# draft1.net
KiCad netlist of a schematic drawn in EAGLE
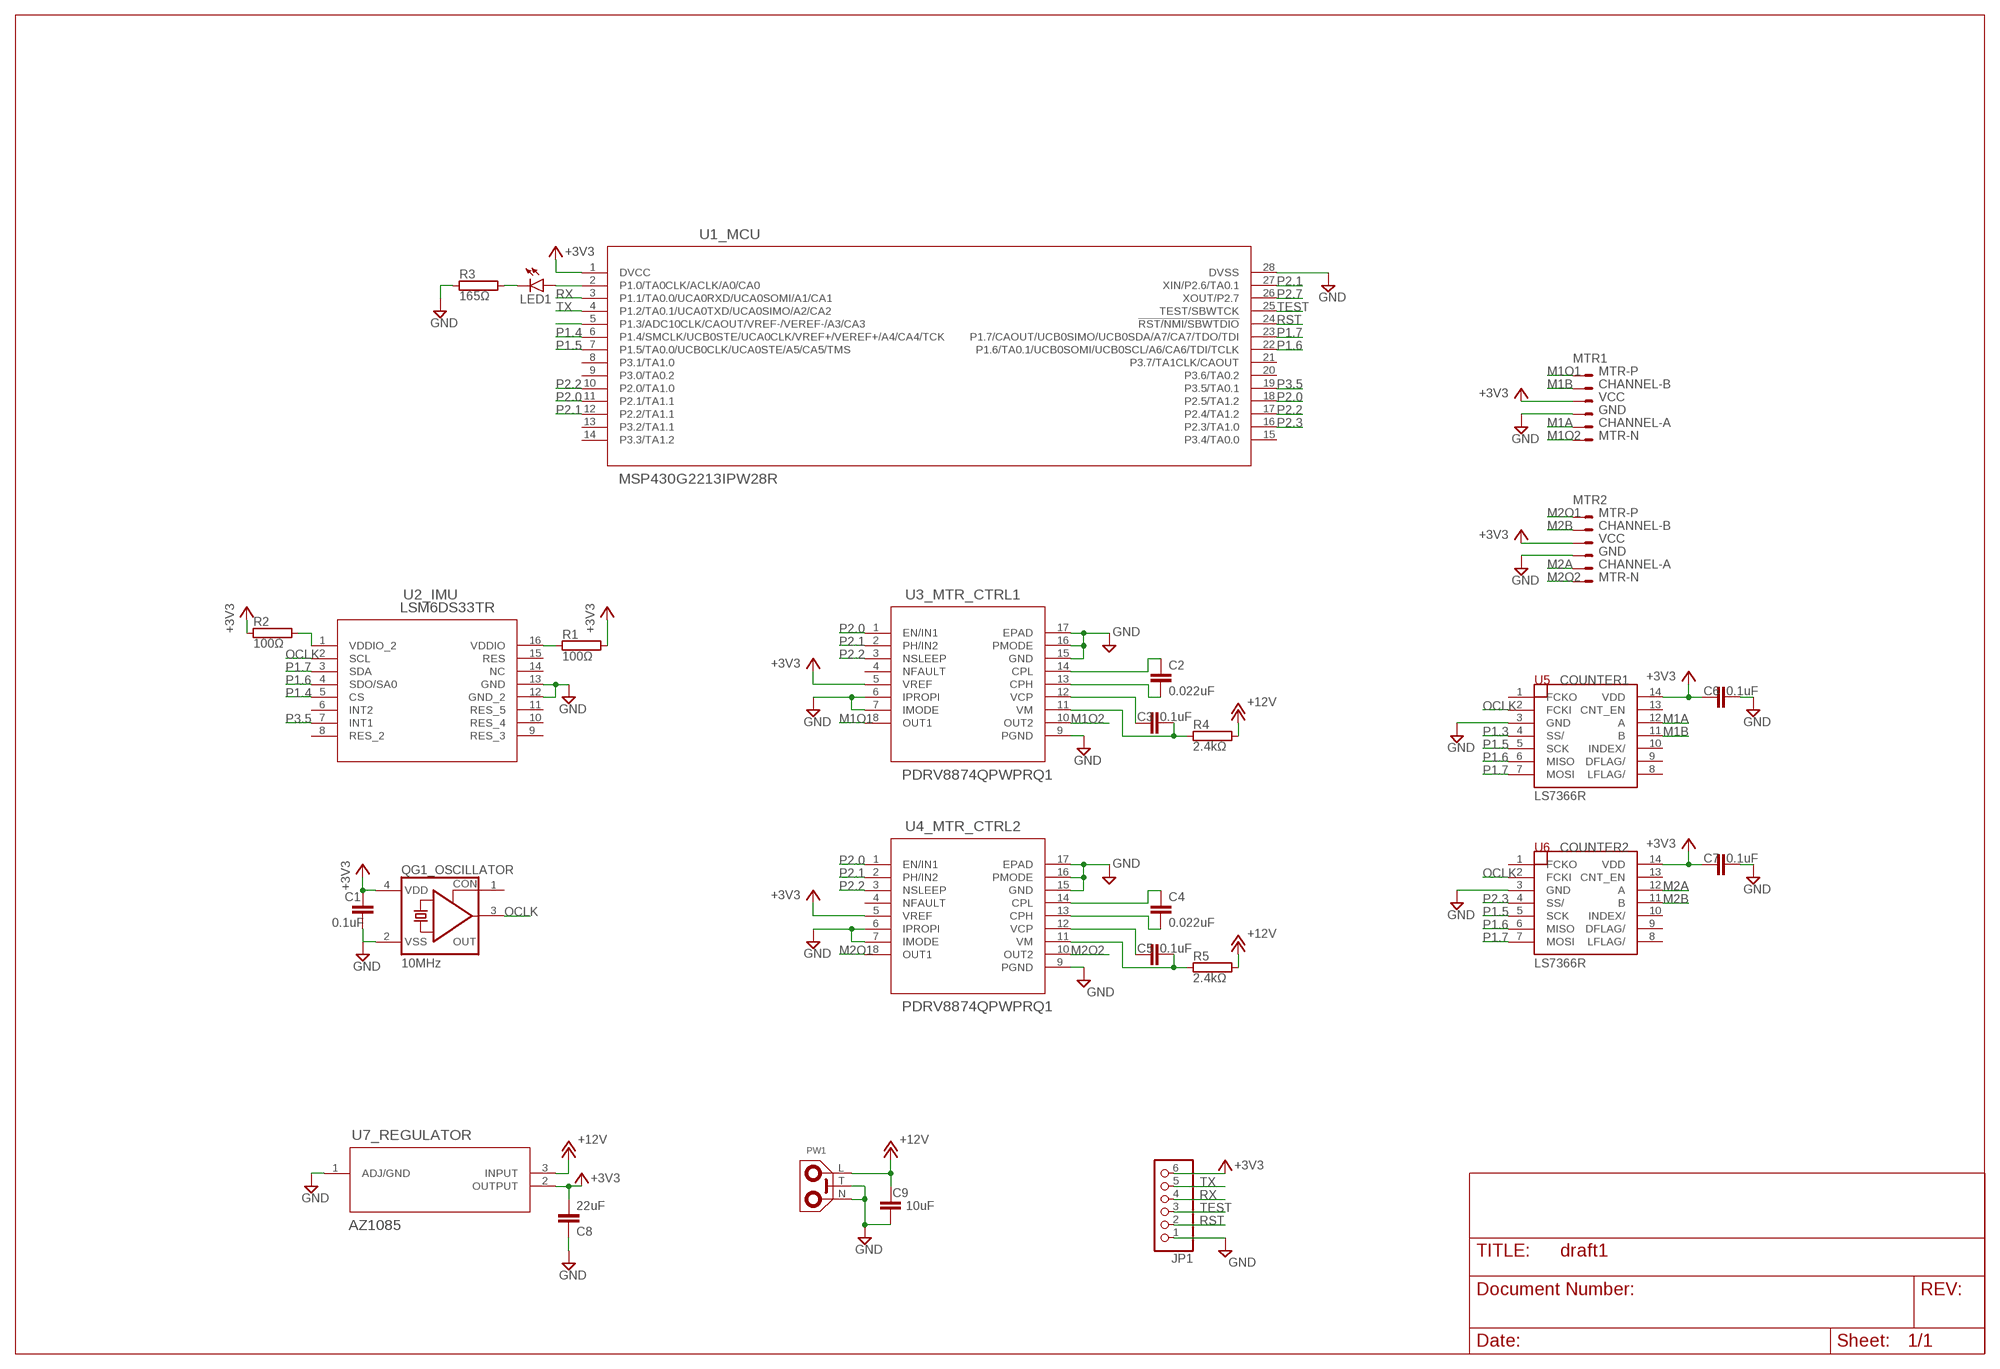
[diagram p0: schematic, sheet 1]

(export (version "E")
  (design (tool "Eeschema 10.0.6"))
  (components
    (comp (ref "C1")
      (value "0.1uF")
      (footprint "eagle-import:C2.5-2")
      (libsource (lib "eagle-import") (part "C2.5/2"))
    )
    (comp (ref "C2")
      (value "0.022uF")
      (footprint "eagle-import:C2.5-2")
      (libsource (lib "eagle-import") (part "C2.5/2"))
    )
    (comp (ref "C3")
      (value "0.1uF")
      (footprint "eagle-import:C2.5-2")
      (libsource (lib "eagle-import") (part "C2.5/2"))
    )
    (comp (ref "C4")
      (value "0.022uF")
      (footprint "eagle-import:C2.5-2")
      (libsource (lib "eagle-import") (part "C2.5/2"))
    )
    (comp (ref "C5")
      (value "0.1uF")
      (footprint "eagle-import:C2.5-2")
      (libsource (lib "eagle-import") (part "C2.5/2"))
    )
    (comp (ref "C6")
      (value "0.1uF")
      (footprint "eagle-import:C2.5-2")
      (libsource (lib "eagle-import") (part "C2.5/2"))
    )
    (comp (ref "C7")
      (value "0.1uF")
      (footprint "eagle-import:C2.5-2")
      (libsource (lib "eagle-import") (part "C2.5/2"))
    )
    (comp (ref "C8")
      (value "22uF")
      (footprint "eagle-import:C2.5-2")
      (libsource (lib "eagle-import") (part "C2.5/2"))
    )
    (comp (ref "C9")
      (value "10uF")
      (footprint "eagle-import:C2.5-2")
      (libsource (lib "eagle-import") (part "C2.5/2"))
    )
    (comp (ref "JP1")
      (value "PINHD-1X6")
      (footprint "eagle-import:1X06")
      (libsource (lib "eagle-import") (part "PINHD-1X6"))
    )
    (comp (ref "LED1")
      (value "LED5MM")
      (footprint "eagle-import:LED5MM")
      (libsource (lib "eagle-import") (part "LED5MM"))
    )
    (comp (ref "MTR1")
      (value "JST-XH-06-PIN-ROUND-PAD")
      (footprint "eagle-import:JST-XH-06-PACKAGE-ROUND-PAD")
      (fields (field (name "MTR1") "1"))
      (libsource (lib "eagle-import") (part "JST-XH-06-PIN-ROUND-PAD"))
    )
    (comp (ref "MTR2")
      (value "JST-XH-06-PIN-ROUND-PAD")
      (footprint "eagle-import:JST-XH-06-PACKAGE-ROUND-PAD")
      (fields (field (name "MTR1") "1"))
      (libsource (lib "eagle-import") (part "JST-XH-06-PIN-ROUND-PAD"))
    )
    (comp (ref "PW1")
      (value "POWER-PM")
      (footprint "eagle-import:POWER-PM")
      (libsource (lib "eagle-import") (part "POWER-PM"))
    )
    (comp (ref "QG1_OSCILLATOR")
      (value "10MHz")
      (footprint "eagle-import:1100S")
      (libsource (lib "eagle-import") (part "CRYSTAL_RES-1100S"))
    )
    (comp (ref "R1")
      (value "100Ω")
      (footprint "eagle-import:AC01")
      (libsource (lib "eagle-import") (part "RAC01"))
    )
    (comp (ref "R2")
      (value "100Ω")
      (footprint "eagle-import:AC01")
      (libsource (lib "eagle-import") (part "RAC01"))
    )
    (comp (ref "R3")
      (value "165Ω")
      (footprint "eagle-import:AC01")
      (libsource (lib "eagle-import") (part "RAC01"))
    )
    (comp (ref "R4")
      (value "2.4kΩ")
      (footprint "eagle-import:AC01")
      (libsource (lib "eagle-import") (part "RAC01"))
    )
    (comp (ref "R5")
      (value "2.4kΩ")
      (footprint "eagle-import:AC01")
      (libsource (lib "eagle-import") (part "RAC01"))
    )
    (comp (ref "U1_MCU")
      (value "MSP430G2213IPW28R")
      (footprint "eagle-import:PW28")
      (fields (field (name "MANUFACTURER") "Texas Instruments"))
      (libsource (lib "eagle-import") (part "MSP430G2213IPW28R"))
    )
    (comp (ref "U2_IMU")
      (value "LSM6DS33TR")
      (footprint "eagle-import:LGA-16L_3X3")
      (fields (field (name "COPYRIGHT") "Copyright (C) 2018 Accelerated Designs. All rights reserved"))
      (libsource (lib "eagle-import") (part "LSM6DS33TR"))
    )
    (comp (ref "U3_MTR_CTRL1")
      (value "PDRV8874QPWPRQ1")
      (footprint "eagle-import:PWP16")
      (fields (field (name "COPYRIGHT") "Copyright (C) 2018 Accelerated Designs. All rights reserved"))
      (libsource (lib "eagle-import") (part "PDRV8874QPWPRQ1"))
    )
    (comp (ref "U4_MTR_CTRL2")
      (value "PDRV8874QPWPRQ1")
      (footprint "eagle-import:PWP16")
      (fields (field (name "COPYRIGHT") "Copyright (C) 2018 Accelerated Designs. All rights reserved"))
      (libsource (lib "eagle-import") (part "PDRV8874QPWPRQ1"))
    )
    (comp (ref "U5")
      (value "LS7366R")
      (footprint "eagle-import:SO14")
      (libsource (lib "eagle-import") (part "LS7366R"))
    )
    (comp (ref "U6")
      (value "LS7366R")
      (footprint "eagle-import:SO14")
      (libsource (lib "eagle-import") (part "LS7366R"))
    )
    (comp (ref "U7_REGULATOR")
      (value "AZ1085")
      (footprint "eagle-import:TO-263_DIO")
      (fields (field (name "MANUFACTURER_PART_NUMBER") "AZ1085CS-2.5TRE1"))
      (libsource (lib "eagle-import") (part "AZ1085"))
    )
  )
  (nets
    (net (code "1") (name "+3V3") (class "Default")
      (node (ref "C1") (pin "1") (pinfunction "1_1") (pintype "passive"))
      (node (ref "C6") (pin "1") (pinfunction "1_1") (pintype "passive"))
      (node (ref "C7") (pin "1") (pinfunction "1_1") (pintype "passive"))
      (node (ref "C8") (pin "2") (pinfunction "2_2") (pintype "passive"))
      (node (ref "JP1") (pin "6") (pinfunction "6_6") (pintype "passive"))
      (node (ref "MTR1") (pin "3") (pinfunction "S_3") (pintype "passive"))
      (node (ref "MTR2") (pin "3") (pinfunction "S_3") (pintype "passive"))
      (node (ref "QG1_OSCILLATOR") (pin "4") (pinfunction "VDD_4") (pintype "power_in"))
      (node (ref "R1") (pin "2") (pinfunction "2_2") (pintype "passive"))
      (node (ref "R2") (pin "1") (pinfunction "1_1") (pintype "passive"))
      (node (ref "U1_MCU") (pin "1") (pinfunction "DVCC_1") (pintype "power_in"))
      (node (ref "U3_MTR_CTRL1") (pin "5") (pinfunction "VREF_5") (pintype "input"))
      (node (ref "U4_MTR_CTRL2") (pin "5") (pinfunction "VREF_5") (pintype "input"))
      (node (ref "U5") (pin "14") (pinfunction "VDD_14") (pintype "bidirectional"))
      (node (ref "U6") (pin "14") (pinfunction "VDD_14") (pintype "bidirectional"))
      (node (ref "U7_REGULATOR") (pin "2") (pinfunction "OUTPUT_2") (pintype "output"))
    )
    (net (code "2") (name "+12V") (class "Default")
      (node (ref "C9") (pin "1") (pinfunction "1_1") (pintype "passive"))
      (node (ref "PW1") (pin "L") (pinfunction "1_L") (pintype "passive"))
      (node (ref "R4") (pin "2") (pinfunction "2_2") (pintype "passive"))
      (node (ref "R5") (pin "2") (pinfunction "2_2") (pintype "passive"))
      (node (ref "U7_REGULATOR") (pin "3") (pinfunction "INPUT_3") (pintype "input"))
    )
    (net (code "3") (name "/M1A") (class "Default")
      (node (ref "MTR1") (pin "5") (pinfunction "S_5") (pintype "passive"))
      (node (ref "U5") (pin "12") (pinfunction "A_12") (pintype "bidirectional"))
    )
    (net (code "4") (name "/M1B") (class "Default")
      (node (ref "MTR1") (pin "2") (pinfunction "S_2") (pintype "passive"))
      (node (ref "U5") (pin "11") (pinfunction "B_11") (pintype "bidirectional"))
    )
    (net (code "5") (name "/M1O1") (class "Default")
      (node (ref "MTR1") (pin "1") (pinfunction "S_1") (pintype "passive"))
      (node (ref "U3_MTR_CTRL1") (pin "8") (pinfunction "OUT1_8") (pintype "output"))
    )
    (net (code "6") (name "/M1O2") (class "Default")
      (node (ref "MTR1") (pin "6") (pinfunction "S_6") (pintype "passive"))
      (node (ref "U3_MTR_CTRL1") (pin "10") (pinfunction "OUT2_10") (pintype "output"))
    )
    (net (code "7") (name "/M2A") (class "Default")
      (node (ref "MTR2") (pin "5") (pinfunction "S_5") (pintype "passive"))
      (node (ref "U6") (pin "12") (pinfunction "A_12") (pintype "bidirectional"))
    )
    (net (code "8") (name "/M2B") (class "Default")
      (node (ref "MTR2") (pin "2") (pinfunction "S_2") (pintype "passive"))
      (node (ref "U6") (pin "11") (pinfunction "B_11") (pintype "bidirectional"))
    )
    (net (code "9") (name "/M2O1") (class "Default")
      (node (ref "MTR2") (pin "1") (pinfunction "S_1") (pintype "passive"))
      (node (ref "U4_MTR_CTRL2") (pin "8") (pinfunction "OUT1_8") (pintype "output"))
    )
    (net (code "10") (name "/M2O2") (class "Default")
      (node (ref "MTR2") (pin "6") (pinfunction "S_6") (pintype "passive"))
      (node (ref "U4_MTR_CTRL2") (pin "10") (pinfunction "OUT2_10") (pintype "output"))
    )
    (net (code "11") (name "/OCLK") (class "Default")
      (node (ref "QG1_OSCILLATOR") (pin "3") (pinfunction "OUT_3") (pintype "output"))
      (node (ref "U2_IMU") (pin "2") (pinfunction "SCL_2") (pintype "bidirectional"))
      (node (ref "U5") (pin "2") (pinfunction "FCKI_2") (pintype "bidirectional"))
      (node (ref "U6") (pin "2") (pinfunction "FCKI_2") (pintype "bidirectional"))
    )
    (net (code "12") (name "/P1.3") (class "Default")
      (node (ref "U5") (pin "4") (pinfunction "SS/_4") (pintype "bidirectional"))
    )
    (net (code "13") (name "/P1.4") (class "Default")
      (node (ref "U1_MCU") (pin "6") (pinfunction "P1.4/SMCLK/UCB0STE/UCA0CLK/VREF+/VEREF+/A4/CA4/TCK_6") (pintype "bidirectional"))
      (node (ref "U2_IMU") (pin "5") (pinfunction "CS_5") (pintype "bidirectional"))
    )
    (net (code "14") (name "/P1.5") (class "Default")
      (node (ref "U1_MCU") (pin "7") (pinfunction "P1.5/TA0.0/UCB0CLK/UCA0STE/A5/CA5/TMS_7") (pintype "bidirectional"))
      (node (ref "U5") (pin "5") (pinfunction "SCK_5") (pintype "bidirectional"))
      (node (ref "U6") (pin "5") (pinfunction "SCK_5") (pintype "bidirectional"))
    )
    (net (code "15") (name "/P1.6") (class "Default")
      (node (ref "U1_MCU") (pin "22") (pinfunction "P1.6/TA0.1/UCB0SOMI/UCB0SCL/A6/CA6/TDI/TCLK_22") (pintype "bidirectional"))
      (node (ref "U2_IMU") (pin "4") (pinfunction "SDO/SA0_4") (pintype "bidirectional"))
      (node (ref "U5") (pin "6") (pinfunction "MISO_6") (pintype "bidirectional"))
      (node (ref "U6") (pin "6") (pinfunction "MISO_6") (pintype "bidirectional"))
    )
    (net (code "16") (name "/P1.7") (class "Default")
      (node (ref "U1_MCU") (pin "23") (pinfunction "P1.7/CAOUT/UCB0SIMO/UCB0SDA/A7/CA7/TDO/TDI_23") (pintype "bidirectional"))
      (node (ref "U2_IMU") (pin "3") (pinfunction "SDA_3") (pintype "bidirectional"))
      (node (ref "U5") (pin "7") (pinfunction "MOSI_7") (pintype "bidirectional"))
      (node (ref "U6") (pin "7") (pinfunction "MOSI_7") (pintype "bidirectional"))
    )
    (net (code "17") (name "/P2.0") (class "Default")
      (node (ref "U1_MCU") (pin "11") (pinfunction "P2.1/TA1.1_11") (pintype "bidirectional"))
      (node (ref "U1_MCU") (pin "18") (pinfunction "P2.5/TA1.2_18") (pintype "bidirectional"))
      (node (ref "U3_MTR_CTRL1") (pin "1") (pinfunction "EN/IN1_1") (pintype "input"))
      (node (ref "U4_MTR_CTRL2") (pin "1") (pinfunction "EN/IN1_1") (pintype "input"))
    )
    (net (code "18") (name "/P2.1") (class "Default")
      (node (ref "U1_MCU") (pin "12") (pinfunction "P2.2/TA1.1_12") (pintype "bidirectional"))
      (node (ref "U1_MCU") (pin "27") (pinfunction "XIN/P2.6/TA0.1_27") (pintype "bidirectional"))
      (node (ref "U3_MTR_CTRL1") (pin "2") (pinfunction "PH/IN2_2") (pintype "input"))
      (node (ref "U4_MTR_CTRL2") (pin "2") (pinfunction "PH/IN2_2") (pintype "input"))
    )
    (net (code "19") (name "/P2.2") (class "Default")
      (node (ref "U1_MCU") (pin "10") (pinfunction "P2.0/TA1.0_10") (pintype "bidirectional"))
      (node (ref "U1_MCU") (pin "17") (pinfunction "P2.4/TA1.2_17") (pintype "bidirectional"))
      (node (ref "U3_MTR_CTRL1") (pin "3") (pinfunction "NSLEEP_3") (pintype "input"))
      (node (ref "U4_MTR_CTRL2") (pin "3") (pinfunction "NSLEEP_3") (pintype "input"))
    )
    (net (code "20") (name "/P2.3") (class "Default")
      (node (ref "U1_MCU") (pin "16") (pinfunction "P2.3/TA1.0_16") (pintype "bidirectional"))
      (node (ref "U6") (pin "4") (pinfunction "SS/_4") (pintype "bidirectional"))
    )
    (net (code "21") (name "/P2.7") (class "Default")
      (node (ref "U1_MCU") (pin "26") (pinfunction "XOUT/P2.7_26") (pintype "bidirectional"))
    )
    (net (code "22") (name "/P3.5") (class "Default")
      (node (ref "U1_MCU") (pin "19") (pinfunction "P3.5/TA0.1_19") (pintype "bidirectional"))
      (node (ref "U2_IMU") (pin "7") (pinfunction "INT1_7") (pintype "bidirectional"))
    )
    (net (code "23") (name "/RST") (class "Default")
      (node (ref "JP1") (pin "2") (pinfunction "2_2") (pintype "passive"))
      (node (ref "U1_MCU") (pin "24") (pinfunction "~{RST/NMI/SBWTDIO}_24") (pintype "bidirectional"))
    )
    (net (code "24") (name "/RX") (class "Default")
      (node (ref "JP1") (pin "4") (pinfunction "4_4") (pintype "passive"))
      (node (ref "U1_MCU") (pin "3") (pinfunction "P1.1/TA0.0/UCA0RXD/UCA0SOMI/A1/CA1_3") (pintype "bidirectional"))
    )
    (net (code "25") (name "/TEST") (class "Default")
      (node (ref "JP1") (pin "3") (pinfunction "3_3") (pintype "passive"))
      (node (ref "U1_MCU") (pin "25") (pinfunction "TEST/SBWTCK_25") (pintype "bidirectional"))
    )
    (net (code "26") (name "/TX") (class "Default")
      (node (ref "JP1") (pin "5") (pinfunction "5_5") (pintype "passive"))
      (node (ref "U1_MCU") (pin "4") (pinfunction "P1.2/TA0.1/UCA0TXD/UCA0SIMO/A2/CA2_4") (pintype "bidirectional"))
    )
    (net (code "27") (name "GND") (class "Default")
      (node (ref "C1") (pin "2") (pinfunction "2_2") (pintype "passive"))
      (node (ref "C6") (pin "2") (pinfunction "2_2") (pintype "passive"))
      (node (ref "C7") (pin "2") (pinfunction "2_2") (pintype "passive"))
      (node (ref "C8") (pin "1") (pinfunction "1_1") (pintype "passive"))
      (node (ref "C9") (pin "2") (pinfunction "2_2") (pintype "passive"))
      (node (ref "JP1") (pin "1") (pinfunction "1_1") (pintype "passive"))
      (node (ref "MTR1") (pin "4") (pinfunction "S_4") (pintype "passive"))
      (node (ref "MTR2") (pin "4") (pinfunction "S_4") (pintype "passive"))
      (node (ref "PW1") (pin "N") (pinfunction "2_N") (pintype "passive"))
      (node (ref "PW1") (pin "T") (pinfunction "T_T") (pintype "passive"))
      (node (ref "QG1_OSCILLATOR") (pin "2") (pinfunction "VSS_2") (pintype "power_in"))
      (node (ref "R3") (pin "1") (pinfunction "1_1") (pintype "passive"))
      (node (ref "U1_MCU") (pin "28") (pinfunction "DVSS_28") (pintype "power_in"))
      (node (ref "U2_IMU") (pin "12") (pinfunction "GND_2_12") (pintype "power_in"))
      (node (ref "U2_IMU") (pin "13") (pinfunction "GND_13") (pintype "power_in"))
      (node (ref "U3_MTR_CTRL1") (pin "15") (pinfunction "GND_15") (pintype "power_in"))
      (node (ref "U3_MTR_CTRL1") (pin "16") (pinfunction "PMODE_16") (pintype "input"))
      (node (ref "U3_MTR_CTRL1") (pin "17") (pinfunction "EPAD_17") (pintype "passive"))
      (node (ref "U3_MTR_CTRL1") (pin "6") (pinfunction "IPROPI_6") (pintype "output"))
      (node (ref "U3_MTR_CTRL1") (pin "7") (pinfunction "IMODE_7") (pintype "input"))
      (node (ref "U3_MTR_CTRL1") (pin "9") (pinfunction "PGND_9") (pintype "power_in"))
      (node (ref "U4_MTR_CTRL2") (pin "15") (pinfunction "GND_15") (pintype "power_in"))
      (node (ref "U4_MTR_CTRL2") (pin "16") (pinfunction "PMODE_16") (pintype "input"))
      (node (ref "U4_MTR_CTRL2") (pin "17") (pinfunction "EPAD_17") (pintype "passive"))
      (node (ref "U4_MTR_CTRL2") (pin "6") (pinfunction "IPROPI_6") (pintype "output"))
      (node (ref "U4_MTR_CTRL2") (pin "7") (pinfunction "IMODE_7") (pintype "input"))
      (node (ref "U4_MTR_CTRL2") (pin "9") (pinfunction "PGND_9") (pintype "power_in"))
      (node (ref "U5") (pin "3") (pinfunction "GND_3") (pintype "bidirectional"))
      (node (ref "U6") (pin "3") (pinfunction "GND_3") (pintype "bidirectional"))
      (node (ref "U7_REGULATOR") (pin "1") (pinfunction "ADJ/GND_1") (pintype "bidirectional"))
    )
    (net (code "28") (name "Net-(LED1-C)") (class "Default")
      (node (ref "LED1") (pin "K") (pinfunction "C_K") (pintype "passive"))
      (node (ref "R3") (pin "2") (pinfunction "2_2") (pintype "passive"))
    )
    (net (code "29") (name "Net-(U1_MCU-P1.0{slash}TA0CLK{slash}ACLK{slash}A0{slash}CA0)") (class "Default")
      (node (ref "LED1") (pin "A") (pinfunction "A_A") (pintype "passive"))
      (node (ref "U1_MCU") (pin "2") (pinfunction "P1.0/TA0CLK/ACLK/A0/CA0_2") (pintype "bidirectional"))
    )
    (net (code "30") (name "Net-(U2_IMU-VDDIO)") (class "Default")
      (node (ref "R1") (pin "1") (pinfunction "1_1") (pintype "passive"))
      (node (ref "U2_IMU") (pin "16") (pinfunction "VDDIO_16") (pintype "power_in"))
    )
    (net (code "31") (name "Net-(U2_IMU-VDDIO_2)") (class "Default")
      (node (ref "R2") (pin "2") (pinfunction "2_2") (pintype "passive"))
      (node (ref "U2_IMU") (pin "1") (pinfunction "VDDIO_2_1") (pintype "power_in"))
    )
    (net (code "32") (name "Net-(U3_MTR_CTRL1-CPH)") (class "Default")
      (node (ref "C2") (pin "2") (pinfunction "2_2") (pintype "passive"))
      (node (ref "U3_MTR_CTRL1") (pin "13") (pinfunction "CPH_13") (pintype "passive"))
    )
    (net (code "33") (name "Net-(U3_MTR_CTRL1-CPL)") (class "Default")
      (node (ref "C2") (pin "1") (pinfunction "1_1") (pintype "passive"))
      (node (ref "U3_MTR_CTRL1") (pin "14") (pinfunction "CPL_14") (pintype "passive"))
    )
    (net (code "34") (name "Net-(U3_MTR_CTRL1-VCP)") (class "Default")
      (node (ref "C3") (pin "1") (pinfunction "1_1") (pintype "passive"))
      (node (ref "U3_MTR_CTRL1") (pin "12") (pinfunction "VCP_12") (pintype "output"))
    )
    (net (code "35") (name "Net-(U3_MTR_CTRL1-VM)") (class "Default")
      (node (ref "C3") (pin "2") (pinfunction "2_2") (pintype "passive"))
      (node (ref "R4") (pin "1") (pinfunction "1_1") (pintype "passive"))
      (node (ref "U3_MTR_CTRL1") (pin "11") (pinfunction "VM_11") (pintype "input"))
    )
    (net (code "36") (name "Net-(U4_MTR_CTRL2-CPH)") (class "Default")
      (node (ref "C4") (pin "2") (pinfunction "2_2") (pintype "passive"))
      (node (ref "U4_MTR_CTRL2") (pin "13") (pinfunction "CPH_13") (pintype "passive"))
    )
    (net (code "37") (name "Net-(U4_MTR_CTRL2-CPL)") (class "Default")
      (node (ref "C4") (pin "1") (pinfunction "1_1") (pintype "passive"))
      (node (ref "U4_MTR_CTRL2") (pin "14") (pinfunction "CPL_14") (pintype "passive"))
    )
    (net (code "38") (name "Net-(U4_MTR_CTRL2-VCP)") (class "Default")
      (node (ref "C5") (pin "1") (pinfunction "1_1") (pintype "passive"))
      (node (ref "U4_MTR_CTRL2") (pin "12") (pinfunction "VCP_12") (pintype "output"))
    )
    (net (code "39") (name "Net-(U4_MTR_CTRL2-VM)") (class "Default")
      (node (ref "C5") (pin "2") (pinfunction "2_2") (pintype "passive"))
      (node (ref "R5") (pin "1") (pinfunction "1_1") (pintype "passive"))
      (node (ref "U4_MTR_CTRL2") (pin "11") (pinfunction "VM_11") (pintype "input"))
    )
    (net (code "40") (name "unconnected-(QG1_OSCILLATOR-CON-Pad1)") (class "Default")
      (node (ref "QG1_OSCILLATOR") (pin "1") (pinfunction "CON_1") (pintype "input"))
    )
    (net (code "41") (name "unconnected-(U1_MCU-P1.3{slash}ADC10CLK{slash}CAOUT{slash}VREF-{slash}VEREF-{slash}A3{slash}CA3-Pad5)") (class "Default")
      (node (ref "U1_MCU") (pin "5") (pinfunction "P1.3/ADC10CLK/CAOUT/VREF-/VEREF-/A3/CA3_5") (pintype "bidirectional"))
    )
    (net (code "42") (name "unconnected-(U1_MCU-P3.0{slash}TA0.2-Pad9)") (class "Default")
      (node (ref "U1_MCU") (pin "9") (pinfunction "P3.0/TA0.2_9") (pintype "bidirectional"))
    )
    (net (code "43") (name "unconnected-(U1_MCU-P3.1{slash}TA1.0-Pad8)") (class "Default")
      (node (ref "U1_MCU") (pin "8") (pinfunction "P3.1/TA1.0_8") (pintype "bidirectional"))
    )
    (net (code "44") (name "unconnected-(U1_MCU-P3.2{slash}TA1.1-Pad13)") (class "Default")
      (node (ref "U1_MCU") (pin "13") (pinfunction "P3.2/TA1.1_13") (pintype "bidirectional"))
    )
    (net (code "45") (name "unconnected-(U1_MCU-P3.3{slash}TA1.2-Pad14)") (class "Default")
      (node (ref "U1_MCU") (pin "14") (pinfunction "P3.3/TA1.2_14") (pintype "bidirectional"))
    )
    (net (code "46") (name "unconnected-(U1_MCU-P3.4{slash}TA0.0-Pad15)") (class "Default")
      (node (ref "U1_MCU") (pin "15") (pinfunction "P3.4/TA0.0_15") (pintype "bidirectional"))
    )
    (net (code "47") (name "unconnected-(U1_MCU-P3.6{slash}TA0.2-Pad20)") (class "Default")
      (node (ref "U1_MCU") (pin "20") (pinfunction "P3.6/TA0.2_20") (pintype "bidirectional"))
    )
    (net (code "48") (name "unconnected-(U1_MCU-P3.7{slash}TA1CLK{slash}CAOUT-Pad21)") (class "Default")
      (node (ref "U1_MCU") (pin "21") (pinfunction "P3.7/TA1CLK/CAOUT_21") (pintype "bidirectional"))
    )
    (net (code "49") (name "unconnected-(U2_IMU-INT2-Pad6)") (class "Default")
      (node (ref "U2_IMU") (pin "6") (pinfunction "INT2_6") (pintype "bidirectional"))
    )
    (net (code "50") (name "unconnected-(U2_IMU-NC-Pad14)") (class "Default")
      (node (ref "U2_IMU") (pin "14") (pinfunction "NC_14") (pintype "no_connect"))
    )
    (net (code "51") (name "unconnected-(U2_IMU-RES-Pad15)") (class "Default")
      (node (ref "U2_IMU") (pin "15") (pinfunction "RES_15") (pintype "passive"))
    )
    (net (code "52") (name "unconnected-(U2_IMU-RES_2-Pad8)") (class "Default")
      (node (ref "U2_IMU") (pin "8") (pinfunction "RES_2_8") (pintype "passive"))
    )
    (net (code "53") (name "unconnected-(U2_IMU-RES_3-Pad9)") (class "Default")
      (node (ref "U2_IMU") (pin "9") (pinfunction "RES_3_9") (pintype "passive"))
    )
    (net (code "54") (name "unconnected-(U2_IMU-RES_4-Pad10)") (class "Default")
      (node (ref "U2_IMU") (pin "10") (pinfunction "RES_4_10") (pintype "passive"))
    )
    (net (code "55") (name "unconnected-(U2_IMU-RES_5-Pad11)") (class "Default")
      (node (ref "U2_IMU") (pin "11") (pinfunction "RES_5_11") (pintype "passive"))
    )
    (net (code "56") (name "unconnected-(U3_MTR_CTRL1-NFAULT-Pad4)") (class "Default")
      (node (ref "U3_MTR_CTRL1") (pin "4") (pinfunction "NFAULT_4") (pintype "output"))
    )
    (net (code "57") (name "unconnected-(U4_MTR_CTRL2-NFAULT-Pad4)") (class "Default")
      (node (ref "U4_MTR_CTRL2") (pin "4") (pinfunction "NFAULT_4") (pintype "output"))
    )
    (net (code "58") (name "unconnected-(U5-CNT_EN-Pad13)") (class "Default")
      (node (ref "U5") (pin "13") (pinfunction "CNT_EN_13") (pintype "bidirectional"))
    )
    (net (code "59") (name "unconnected-(U5-DFLAG{slash}-Pad9)") (class "Default")
      (node (ref "U5") (pin "9") (pinfunction "DFLAG/_9") (pintype "bidirectional"))
    )
    (net (code "60") (name "unconnected-(U5-FCKO-Pad1)") (class "Default")
      (node (ref "U5") (pin "1") (pinfunction "FCKO_1") (pintype "bidirectional"))
    )
    (net (code "61") (name "unconnected-(U5-INDEX{slash}-Pad10)") (class "Default")
      (node (ref "U5") (pin "10") (pinfunction "INDEX/_10") (pintype "bidirectional"))
    )
    (net (code "62") (name "unconnected-(U5-LFLAG{slash}-Pad8)") (class "Default")
      (node (ref "U5") (pin "8") (pinfunction "LFLAG/_8") (pintype "bidirectional"))
    )
    (net (code "63") (name "unconnected-(U6-CNT_EN-Pad13)") (class "Default")
      (node (ref "U6") (pin "13") (pinfunction "CNT_EN_13") (pintype "bidirectional"))
    )
    (net (code "64") (name "unconnected-(U6-DFLAG{slash}-Pad9)") (class "Default")
      (node (ref "U6") (pin "9") (pinfunction "DFLAG/_9") (pintype "bidirectional"))
    )
    (net (code "65") (name "unconnected-(U6-FCKO-Pad1)") (class "Default")
      (node (ref "U6") (pin "1") (pinfunction "FCKO_1") (pintype "bidirectional"))
    )
    (net (code "66") (name "unconnected-(U6-INDEX{slash}-Pad10)") (class "Default")
      (node (ref "U6") (pin "10") (pinfunction "INDEX/_10") (pintype "bidirectional"))
    )
    (net (code "67") (name "unconnected-(U6-LFLAG{slash}-Pad8)") (class "Default")
      (node (ref "U6") (pin "8") (pinfunction "LFLAG/_8") (pintype "bidirectional"))
    )
  )
)
